# LoRaMicroClimate.net
KiCad netlist of a schematic drawn in Altium Designer
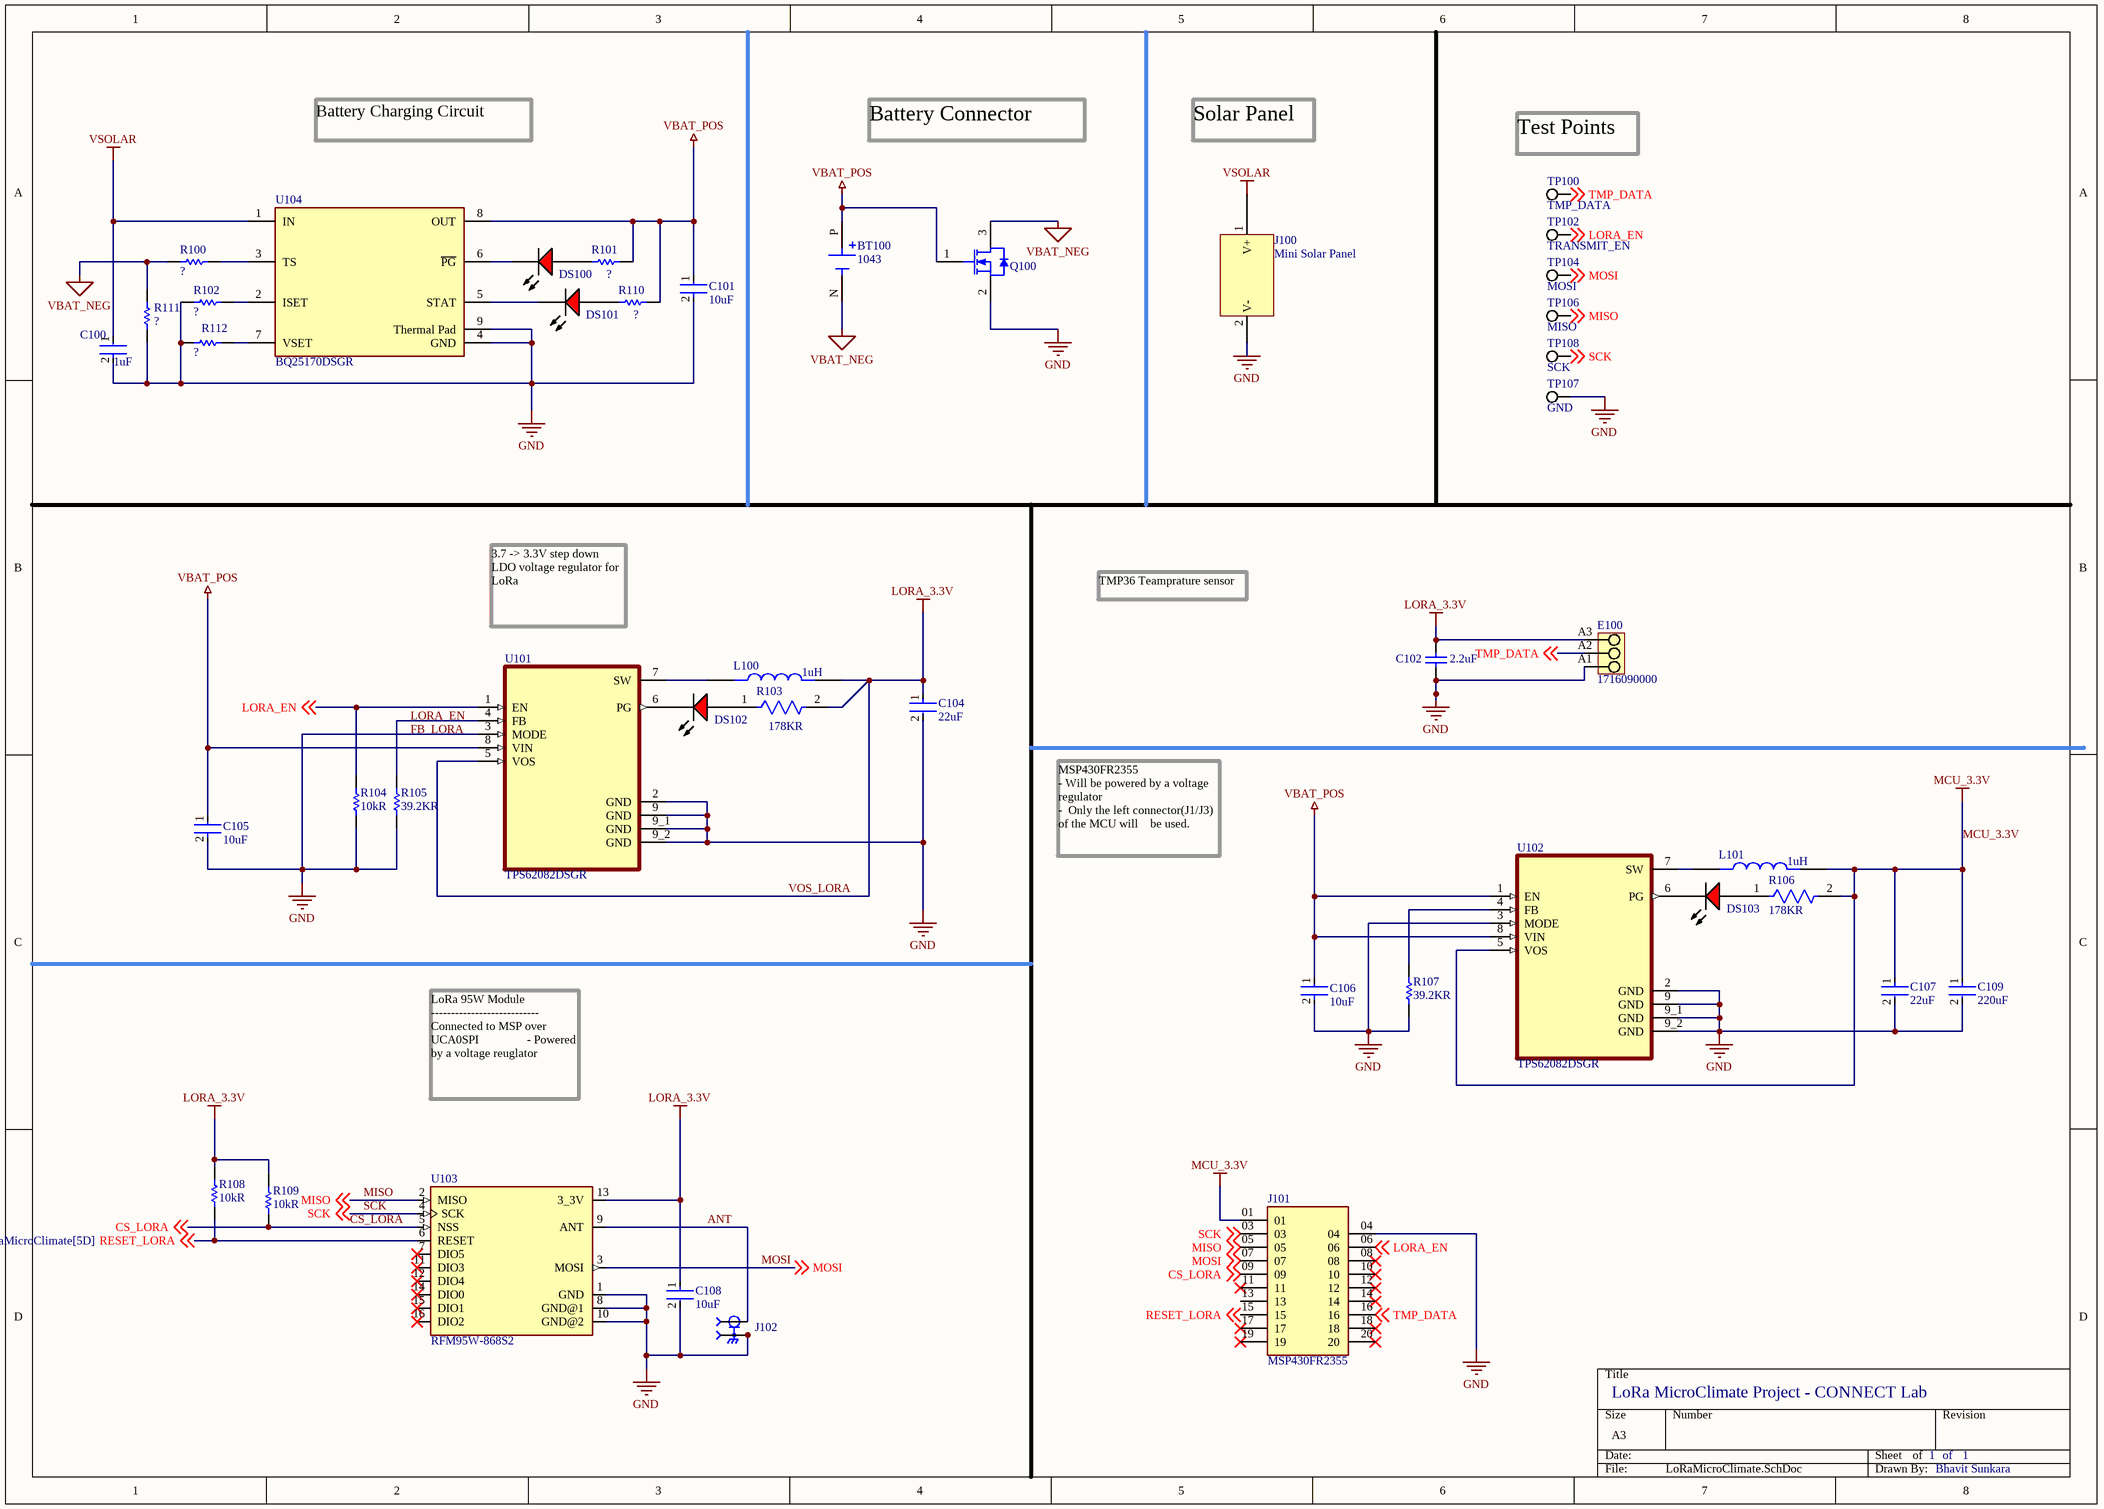
[diagram p0: LoRaMicroClimate.SchDoc]

(export (version "E")
  (design (tool "Eeschema 10.0.6"))
  (components
    (comp (ref "BT100")
      (value "1043")
      (footprint "BAT_1043")
      (description "Battery Holder (Open) 18650 1 Cell PC Pin")
      (libsource (lib "1043") (part "1043"))
    )
    (comp (ref "C100")
      (value "1uF")
      (footprint "FP-C1608-080-0_1-MFG")
      (description "Multilayer Ceramic Capacitors 10μF ±10% 10V X5R SMD 0603")
      (fields (field (name "VOLTAGE") "10V") (field (name "TOLERANCE") "10%"))
      (libsource (lib "Altium Content Vault") (part "236180d848d6139a670b325ea6854c9"))
    )
    (comp (ref "C101")
      (value "10uF")
      (footprint "FP-C1608-080-0_1-MFG")
      (description "Multilayer Ceramic Capacitors 10μF ±10% 10V X5R SMD 0603")
      (fields (field (name "VOLTAGE") "10V") (field (name "TOLERANCE") "10%"))
      (libsource (lib "Altium Content Vault") (part "236180d848d6139a670b325ea6854c9"))
    )
    (comp (ref "C102")
      (value "2.2uF")
      (footprint "CAPC2113X120X50ML20T30")
      (fields
        (field (name "PART NUMBER") "TAJR225M010RNJ")
        (field (name "MANUFACTURER") "AVX Interconnect / Elco")
      )
      (libsource (lib "Altium Content Vault") (part "CAP"))
    )
    (comp (ref "C104")
      (value "22uF")
      (footprint "FP-GRM21B-0_15-MFG")
      (description "Chip Multilayer Ceramic Capacitors for General Purpose, 0805, 22uF, X5R, 15%, 20%, 6.3V")
      (fields (field (name "VOLTAGE") "6.3V") (field (name "TOLERANCE") "20%"))
      (libsource (lib "Altium Content Vault") (part "b4654b650e69147ec39a6b967a45e02"))
    )
    (comp (ref "C105")
      (value "10uF")
      (footprint "FP-C1608-080-0_1-MFG")
      (description "Multilayer Ceramic Capacitors 10μF ±10% 10V X5R SMD 0603")
      (fields (field (name "VOLTAGE") "10V") (field (name "TOLERANCE") "10%"))
      (libsource (lib "Altium Content Vault") (part "236180d848d6139a670b325ea6854c9"))
    )
    (comp (ref "C106")
      (value "10uF")
      (footprint "FP-C1608-080-0_1-MFG")
      (description "Multilayer Ceramic Capacitors 10μF ±10% 10V X5R SMD 0603")
      (fields (field (name "VOLTAGE") "10V") (field (name "TOLERANCE") "10%"))
      (libsource (lib "Altium Content Vault") (part "236180d848d6139a670b325ea6854c9"))
    )
    (comp (ref "C107")
      (value "22uF")
      (footprint "FP-GRM21B-0_15-MFG")
      (description "Chip Multilayer Ceramic Capacitors for General Purpose, 0805, 22uF, X5R, 15%, 20%, 6.3V")
      (fields (field (name "VOLTAGE") "6.3V") (field (name "TOLERANCE") "20%"))
      (libsource (lib "Altium Content Vault") (part "b4654b650e69147ec39a6b967a45e02"))
    )
    (comp (ref "C108")
      (value "10uF")
      (footprint "FP-CL05A106MP5NUNC-MFG")
      (description "CAP CER 10UF 10V X5R 0402")
      (fields
        (field (name "OCTOPART") "https://octopart.com/cl05a106mp5nunc-samsung-22457395")
        (field (name "TOLERANCE") "20%")
      )
      (libsource (lib "Altium Content Vault") (part "b4654b650e69147ec39a6b967a45e02"))
    )
    (comp (ref "C109")
      (value "220uF")
      (footprint "FP-GRM21B-0_15-MFG")
      (description "Chip Multilayer Ceramic Capacitors for General Purpose, 0805, 22uF, X5R, 15%, 20%, 6.3V")
      (fields (field (name "VOLTAGE") "6.3V") (field (name "TOLERANCE") "20%"))
      (libsource (lib "Altium Content Vault") (part "b4654b650e69147ec39a6b967a45e02"))
    )
    (comp (ref "DS100")
      (value "HSMS-C190")
      (footprint "AVAG-HSMX-C190_V")
      (description "LED Uni-Color Red, 52 mW, 20 mA, -40 to 85 degC, 2-Pin SMD, RoHS, Tape and Reel")
      (fields (field (name "MANUFACTURER") "Avago"))
      (libsource (lib "Altium Content Vault") (part "LED-RED-AK-2"))
    )
    (comp (ref "DS101")
      (value "HSMS-C190")
      (footprint "AVAG-HSMX-C190_V")
      (description "LED Uni-Color Red, 52 mW, 20 mA, -40 to 85 degC, 2-Pin SMD, RoHS, Tape and Reel")
      (fields (field (name "MANUFACTURER") "Avago"))
      (libsource (lib "Altium Content Vault") (part "LED-RED-AK-2"))
    )
    (comp (ref "DS102")
      (value "HSMS-C190")
      (footprint "AVAG-HSMX-C190_V")
      (description "LED Uni-Color Red, 52 mW, 20 mA, -40 to 85 degC, 2-Pin SMD, RoHS, Tape and Reel")
      (fields (field (name "MANUFACTURER") "Avago"))
      (libsource (lib "Altium Content Vault") (part "LED-RED-AK-2"))
    )
    (comp (ref "DS103")
      (value "HSMS-C190")
      (footprint "AVAG-HSMX-C190_V")
      (description "LED Uni-Color Red, 52 mW, 20 mA, -40 to 85 degC, 2-Pin SMD, RoHS, Tape and Reel")
      (fields (field (name "MANUFACTURER") "Avago"))
      (libsource (lib "Altium Content Vault") (part "LED-RED-AK-2"))
    )
    (comp (ref "E100")
      (value "1716090000")
      (footprint "LM_5_08_90_03")
      (description "OMNIMATE Signal - series LM")
      (fields (field (name "MANUFACTURER") "Weidmueller"))
      (libsource (lib "Altium Content Vault") (part "Terminal_03_1x03"))
    )
    (comp (ref "J100")
      (value "Mini Solar Panel")
      (footprint "P122")
      (libsource (lib "WirelessMicroClimate") (part "P122"))
    )
    (comp (ref "J101")
      (value "MSP430FR2355")
      (footprint "SAMTEC_TSW-110-07-G-D-002")
      (fields (field (name "MP") "TSW-110-07-G-D-002"))
      (libsource (lib "TSW-110-07-G-D-002") (part "TSW-110-07-G-D-002"))
    )
    (comp (ref "J102")
      (value "SMA-J-P-X-ST-TH1")
      (footprint "SAMTEC_SMA-J-P-X-ST-TH1")
      (description "SMA STRAIGHT, THROUGH HOLE JACK- 50 OHM")
      (libsource (lib "SMA-J-P-X-ST-TH1") (part "SMA-J-P-X-ST-TH1"))
    )
    (comp (ref "L100")
      (value "1uH")
      (footprint "IND_ASPI-3012S-1R0M-T")
      (description "Inductor Power Shielded Wirewound 1uH 20% 100KHz 2.2A 0.04Ohm DCR 1212 T/R")
      (fields (field (name "MF") "Abracon Corporation") (field (name "MP") "ASPI-3012S-1R0M-T"))
      (libsource (lib "ASPI-3012S-1R0M-T") (part "ASPI-3012S-1R0M-T"))
    )
    (comp (ref "L101")
      (value "1uH")
      (footprint "IND_ASPI-3012S-1R0M-T")
      (description "Inductor Power Shielded Wirewound 1uH 20% 100KHz 2.2A 0.04Ohm DCR 1212 T/R")
      (fields (field (name "MF") "Abracon Corporation") (field (name "MP") "ASPI-3012S-1R0M-T"))
      (libsource (lib "ASPI-3012S-1R0M-T") (part "ASPI-3012S-1R0M-T"))
    )
    (comp (ref "Q100")
      (value "2N7002-T1-E3")
      (footprint "VISH-TO-236-3_A_L")
      (description "N-Channel MOSFET, 115 mA, 60 V, -55 to 150 degC, 3-Pin SOT23, RoHS, Tape and Reel")
      (fields (field (name "MANUFACTURER") "Vishay"))
      (libsource (lib "Altium Content Vault") (part "NEMOS-GSD-3"))
    )
    (comp (ref "R100")
      (value "?")
      (footprint "RESC1005X40X25LL05T10")
      (fields (field (name "PART NUMBER") "RC0402FR-0710KL") (field (name "MANUFACTURER") "Yageo / Phycomp"))
      (libsource (lib "Altium Content Vault") (part "RES"))
    )
    (comp (ref "R101")
      (value "?")
      (footprint "RESC1005X40X25LL05T10")
      (fields (field (name "PART NUMBER") "RC0402FR-0710KL") (field (name "MANUFACTURER") "Yageo / Phycomp"))
      (libsource (lib "Altium Content Vault") (part "RES"))
    )
    (comp (ref "R102")
      (value "?")
      (footprint "RESC1005X40X25LL05T10")
      (fields (field (name "PART NUMBER") "RC0402FR-0710KL") (field (name "MANUFACTURER") "Yageo / Phycomp"))
      (libsource (lib "Altium Content Vault") (part "RES"))
    )
    (comp (ref "R103")
      (value "178KR")
      (footprint "FP-CRCW0603-e3-IPC_A")
      (description "RES Thick Film, 178kΩ, 1%, 0.1W, 100ppm/°C, 0603")
      (fields (field (name "TOLERANCE") "1%"))
      (libsource (lib "Altium Content Vault") (part "1029c3af85768c4190bb7ad29bc67b5"))
    )
    (comp (ref "R104")
      (value "10kR")
      (footprint "RESC1005X40X25LL05T10")
      (fields (field (name "PART NUMBER") "RC0402FR-0710KL") (field (name "MANUFACTURER") "Yageo / Phycomp"))
      (libsource (lib "Altium Content Vault") (part "RES"))
    )
    (comp (ref "R105")
      (value "39.2KR")
      (footprint "RESC1609X50X30LL10T20")
      (fields (field (name "MANUFACTURER") "Vishay Dale") (field (name "PART NUMBER") "CRCW060339K2FKEA"))
      (libsource (lib "Altium Content Vault") (part "RES"))
    )
    (comp (ref "R106")
      (value "178KR")
      (footprint "FP-CRCW0603-e3-IPC_A")
      (description "RES Thick Film, 178kΩ, 1%, 0.1W, 100ppm/°C, 0603")
      (fields (field (name "TOLERANCE") "1%"))
      (libsource (lib "Altium Content Vault") (part "1029c3af85768c4190bb7ad29bc67b5"))
    )
    (comp (ref "R107")
      (value "39.2KR")
      (footprint "RESC1609X50X30LL10T20")
      (fields (field (name "MANUFACTURER") "Vishay Dale") (field (name "PART NUMBER") "CRCW060339K2FKEA"))
      (libsource (lib "Altium Content Vault") (part "RES"))
    )
    (comp (ref "R108")
      (value "10kR")
      (footprint "RESC1005X40X25LL05T10")
      (fields (field (name "PART NUMBER") "RC0402FR-0710KL") (field (name "MANUFACTURER") "Yageo / Phycomp"))
      (libsource (lib "Altium Content Vault") (part "RES"))
    )
    (comp (ref "R109")
      (value "10kR")
      (footprint "RESC1005X40X25LL05T10")
      (fields (field (name "PART NUMBER") "RC0402FR-0710KL") (field (name "MANUFACTURER") "Yageo / Phycomp"))
      (libsource (lib "Altium Content Vault") (part "RES"))
    )
    (comp (ref "R110")
      (value "?")
      (footprint "RESC1005X40X25LL05T10")
      (fields (field (name "PART NUMBER") "RC0402FR-0710KL") (field (name "MANUFACTURER") "Yageo / Phycomp"))
      (libsource (lib "Altium Content Vault") (part "RES"))
    )
    (comp (ref "R111")
      (value "?")
      (footprint "RESC1005X40X25LL05T10")
      (fields (field (name "PART NUMBER") "RC0402FR-0710KL") (field (name "MANUFACTURER") "Yageo / Phycomp"))
      (libsource (lib "Altium Content Vault") (part "RES"))
    )
    (comp (ref "R112")
      (value "?")
      (footprint "RESC1005X40X25LL05T10")
      (fields (field (name "PART NUMBER") "RC0402FR-0710KL") (field (name "MANUFACTURER") "Yageo / Phycomp"))
      (libsource (lib "Altium Content Vault") (part "RES"))
    )
    (comp (ref "TP100")
      (value "TMP_DATA")
      (footprint "KSTN-5019_V")
      (description "Test Point, 1 Position SMD, RoHS, Tape and Reel")
      (libsource (lib "Altium Content Vault") (part "TESTPOINT_WHITE"))
    )
    (comp (ref "TP102")
      (value "TRANSMIT_EN")
      (footprint "KSTN-5019_V")
      (description "Test Point, 1 Position SMD, RoHS, Tape and Reel")
      (libsource (lib "Altium Content Vault") (part "TESTPOINT_WHITE"))
    )
    (comp (ref "TP104")
      (value "MOSI")
      (footprint "KSTN-5019_V")
      (description "Test Point, 1 Position SMD, RoHS, Tape and Reel")
      (libsource (lib "Altium Content Vault") (part "TESTPOINT_WHITE"))
    )
    (comp (ref "TP106")
      (value "MISO")
      (footprint "KSTN-5019_V")
      (description "Test Point, 1 Position SMD, RoHS, Tape and Reel")
      (libsource (lib "Altium Content Vault") (part "TESTPOINT_WHITE"))
    )
    (comp (ref "TP107")
      (value "GND")
      (footprint "KSTN-5019_V")
      (description "Test Point, 1 Position SMD, RoHS, Tape and Reel")
      (libsource (lib "Altium Content Vault") (part "TESTPOINT_WHITE"))
    )
    (comp (ref "TP108")
      (value "SCK")
      (footprint "KSTN-5019_V")
      (description "Test Point, 1 Position SMD, RoHS, Tape and Reel")
      (libsource (lib "Altium Content Vault") (part "TESTPOINT_WHITE"))
    )
    (comp (ref "U101")
      (value "TPS62082DSGR")
      (footprint "SON50P200X200X80-9N")
      (description "1.2A High Efficient Step Down Converter in 2x2mm SON Package. 3.3 Vout (Min) 8-WSON -40 to 125")
      (fields (field (name "MF") "Texas Instruments") (field (name "DIGI-KEY_PART_NUMBER") "296-49331-1-ND"))
      (libsource (lib "TPS62082DSGR") (part "TPS62082DSGR"))
    )
    (comp (ref "U102")
      (value "TPS62082DSGR")
      (footprint "SON50P200X200X80-9N")
      (description "1.2A High Efficient Step Down Converter in 2x2mm SON Package. 3.3 Vout (Min) 8-WSON -40 to 125")
      (fields (field (name "MF") "Texas Instruments") (field (name "DIGI-KEY_PART_NUMBER") "296-49331-1-ND"))
      (libsource (lib "TPS62082DSGR") (part "TPS62082DSGR"))
    )
    (comp (ref "U103")
      (value "RFM95W-868S2")
      (footprint "XCVR_RFM95W-868S2")
      (description "Mod Txrx Lora +20dbm 868mhz Smd")
      (libsource (lib "RFM95W-868S2") (part "RFM95W-868S2"))
    )
    (comp (ref "U104")
      (value "BQ25170DSGR")
      (footprint "FP-DSG0008A-IPC_A")
      (description "800-MA LINEAR BATTERY CHARGER FO")
      (libsource (lib "Altium Content Vault") (part "8a2467e5c458e831b7d8dd803ec95f1"))
    )
  )
  (nets
    (net (code "1") (name "/ANT") (class "Default")
      (node (ref "J102") (pin "1") (pinfunction "1_1") (pintype "passive"))
      (node (ref "U103") (pin "9") (pinfunction "ANT_9") (pintype "passive"))
    )
    (net (code "2") (name "/FB_LORA") (class "Default")
      (node (ref "R105") (pin "1") (pinfunction "1_1") (pintype "passive"))
      (node (ref "U101") (pin "4") (pinfunction "FB_4") (pintype "input"))
    )
    (net (code "3") (name "CS_LORA") (class "Default")
      (node (ref "J101") (pin "09") (pinfunction "09_09") (pintype "passive"))
      (node (ref "R109") (pin "1") (pinfunction "1_1") (pintype "passive"))
      (node (ref "U103") (pin "5") (pinfunction "NSS_5") (pintype "input"))
    )
    (net (code "4") (name "GND") (class "Default")
      (node (ref "C100") (pin "2") (pinfunction "2_2") (pintype "passive"))
      (node (ref "C101") (pin "2") (pinfunction "2_2") (pintype "passive"))
      (node (ref "C102") (pin "1") (pinfunction "1_1") (pintype "passive"))
      (node (ref "C104") (pin "2") (pinfunction "2_2") (pintype "passive"))
      (node (ref "C105") (pin "2") (pinfunction "2_2") (pintype "passive"))
      (node (ref "C106") (pin "2") (pinfunction "2_2") (pintype "passive"))
      (node (ref "C107") (pin "2") (pinfunction "2_2") (pintype "passive"))
      (node (ref "C108") (pin "2") (pinfunction "2_2") (pintype "passive"))
      (node (ref "C109") (pin "2") (pinfunction "2_2") (pintype "passive"))
      (node (ref "E100") (pin "A1") (pinfunction "A1_A1") (pintype "passive"))
      (node (ref "J100") (pin "2") (pinfunction "V-_2") (pintype "passive"))
      (node (ref "J101") (pin "04") (pinfunction "04_04") (pintype "passive"))
      (node (ref "J102") (pin "2") (pinfunction "2_2") (pintype "passive"))
      (node (ref "J102") (pin "3") (pinfunction "2_3") (pintype "passive"))
      (node (ref "J102") (pin "4") (pinfunction "2_4") (pintype "passive"))
      (node (ref "J102") (pin "5") (pinfunction "2_5") (pintype "passive"))
      (node (ref "Q100") (pin "2") (pinfunction "S_2") (pintype "passive"))
      (node (ref "R102") (pin "1") (pinfunction "1_1") (pintype "passive"))
      (node (ref "R104") (pin "2") (pinfunction "2_2") (pintype "passive"))
      (node (ref "R105") (pin "2") (pinfunction "2_2") (pintype "passive"))
      (node (ref "R107") (pin "2") (pinfunction "2_2") (pintype "passive"))
      (node (ref "R111") (pin "1") (pinfunction "1_1") (pintype "passive"))
      (node (ref "R112") (pin "1") (pinfunction "1_1") (pintype "passive"))
      (node (ref "TP107") (pin "1") (pinfunction "1_1") (pintype "passive"))
      (node (ref "U101") (pin "2") (pinfunction "GND_2") (pintype "power_in"))
      (node (ref "U101") (pin "3") (pinfunction "MODE_3") (pintype "input"))
      (node (ref "U101") (pin "9") (pinfunction "GND_9") (pintype "power_in"))
      (node (ref "U101") (pin "9_1") (pinfunction "GND_9_1") (pintype "power_in"))
      (node (ref "U101") (pin "9_2") (pinfunction "GND_9_2") (pintype "power_in"))
      (node (ref "U102") (pin "2") (pinfunction "GND_2") (pintype "power_in"))
      (node (ref "U102") (pin "3") (pinfunction "MODE_3") (pintype "input"))
      (node (ref "U102") (pin "9") (pinfunction "GND_9") (pintype "power_in"))
      (node (ref "U102") (pin "9_1") (pinfunction "GND_9_1") (pintype "power_in"))
      (node (ref "U102") (pin "9_2") (pinfunction "GND_9_2") (pintype "power_in"))
      (node (ref "U103") (pin "1") (pinfunction "GND_1") (pintype "power_in"))
      (node (ref "U103") (pin "10") (pinfunction "GND@2_10") (pintype "power_in"))
      (node (ref "U103") (pin "8") (pinfunction "GND@1_8") (pintype "power_in"))
      (node (ref "U104") (pin "4") (pinfunction "GND_4") (pintype "power_in"))
      (node (ref "U104") (pin "9") (pinfunction "Thermal_Pad_9") (pintype "power_in"))
    )
    (net (code "5") (name "LORA_3.3V") (class "Default")
      (node (ref "C102") (pin "2") (pinfunction "2_2") (pintype "passive"))
      (node (ref "C104") (pin "1") (pinfunction "1_1") (pintype "passive"))
      (node (ref "C108") (pin "1") (pinfunction "1_1") (pintype "passive"))
      (node (ref "E100") (pin "A3") (pinfunction "A3_A3") (pintype "passive"))
      (node (ref "L100") (pin "2") (pinfunction "2_2") (pintype "passive"))
      (node (ref "R103") (pin "2") (pinfunction "2_2") (pintype "passive"))
      (node (ref "R108") (pin "2") (pinfunction "2_2") (pintype "passive"))
      (node (ref "R109") (pin "2") (pinfunction "2_2") (pintype "passive"))
      (node (ref "U101") (pin "5") (pinfunction "VOS_5") (pintype "input"))
      (node (ref "U103") (pin "13") (pinfunction "3_3V_13") (pintype "power_in"))
    )
    (net (code "6") (name "LORA_EN") (class "Default")
      (node (ref "J101") (pin "06") (pinfunction "06_06") (pintype "passive"))
      (node (ref "R104") (pin "1") (pinfunction "1_1") (pintype "passive"))
      (node (ref "TP102") (pin "1") (pinfunction "1_1") (pintype "passive"))
      (node (ref "U101") (pin "1") (pinfunction "EN_1") (pintype "input"))
    )
    (net (code "7") (name "MCU_3.3V") (class "Default")
      (node (ref "C107") (pin "1") (pinfunction "1_1") (pintype "passive"))
      (node (ref "C109") (pin "1") (pinfunction "1_1") (pintype "passive"))
      (node (ref "J101") (pin "01") (pinfunction "01_01") (pintype "passive"))
      (node (ref "L101") (pin "2") (pinfunction "2_2") (pintype "passive"))
      (node (ref "R106") (pin "2") (pinfunction "2_2") (pintype "passive"))
      (node (ref "U102") (pin "5") (pinfunction "VOS_5") (pintype "input"))
    )
    (net (code "8") (name "MISO") (class "Default")
      (node (ref "J101") (pin "05") (pinfunction "05_05") (pintype "passive"))
      (node (ref "TP106") (pin "1") (pinfunction "1_1") (pintype "passive"))
      (node (ref "U103") (pin "2") (pinfunction "MISO_2") (pintype "input"))
    )
    (net (code "9") (name "MOSI") (class "Default")
      (node (ref "J101") (pin "07") (pinfunction "07_07") (pintype "passive"))
      (node (ref "TP104") (pin "1") (pinfunction "1_1") (pintype "passive"))
      (node (ref "U103") (pin "3") (pinfunction "MOSI_3") (pintype "output"))
    )
    (net (code "10") (name "Net-(DS100-A)") (class "Default")
      (node (ref "DS100") (pin "1") (pinfunction "A_1") (pintype "passive"))
      (node (ref "R101") (pin "1") (pinfunction "1_1") (pintype "passive"))
    )
    (net (code "11") (name "Net-(DS100-K)") (class "Default")
      (node (ref "DS100") (pin "2") (pinfunction "K_2") (pintype "passive"))
      (node (ref "U104") (pin "6") (pinfunction "~{PG}_6") (pintype "open_collector"))
    )
    (net (code "12") (name "Net-(DS101-A)") (class "Default")
      (node (ref "DS101") (pin "1") (pinfunction "A_1") (pintype "passive"))
      (node (ref "R110") (pin "1") (pinfunction "1_1") (pintype "passive"))
    )
    (net (code "13") (name "Net-(DS101-K)") (class "Default")
      (node (ref "DS101") (pin "2") (pinfunction "K_2") (pintype "passive"))
      (node (ref "U104") (pin "5") (pinfunction "STAT_5") (pintype "open_collector"))
    )
    (net (code "14") (name "Net-(DS102-A)") (class "Default")
      (node (ref "DS102") (pin "1") (pinfunction "A_1") (pintype "passive"))
      (node (ref "R103") (pin "1") (pinfunction "1_1") (pintype "passive"))
    )
    (net (code "15") (name "Net-(DS102-K)") (class "Default")
      (node (ref "DS102") (pin "2") (pinfunction "K_2") (pintype "passive"))
      (node (ref "U101") (pin "6") (pinfunction "PG_6") (pintype "output"))
    )
    (net (code "16") (name "Net-(DS103-A)") (class "Default")
      (node (ref "DS103") (pin "1") (pinfunction "A_1") (pintype "passive"))
      (node (ref "R106") (pin "1") (pinfunction "1_1") (pintype "passive"))
    )
    (net (code "17") (name "Net-(DS103-K)") (class "Default")
      (node (ref "DS103") (pin "2") (pinfunction "K_2") (pintype "passive"))
      (node (ref "U102") (pin "6") (pinfunction "PG_6") (pintype "output"))
    )
    (net (code "18") (name "Net-(U101-SW)") (class "Default")
      (node (ref "L100") (pin "1") (pinfunction "1_1") (pintype "passive"))
      (node (ref "U101") (pin "7") (pinfunction "SW_7") (pintype "power_in"))
    )
    (net (code "19") (name "Net-(U102-FB)") (class "Default")
      (node (ref "R107") (pin "1") (pinfunction "1_1") (pintype "passive"))
      (node (ref "U102") (pin "4") (pinfunction "FB_4") (pintype "input"))
    )
    (net (code "20") (name "Net-(U102-SW)") (class "Default")
      (node (ref "L101") (pin "1") (pinfunction "1_1") (pintype "passive"))
      (node (ref "U102") (pin "7") (pinfunction "SW_7") (pintype "power_in"))
    )
    (net (code "21") (name "Net-(U104-ISET)") (class "Default")
      (node (ref "R102") (pin "2") (pinfunction "2_2") (pintype "passive"))
      (node (ref "U104") (pin "2") (pinfunction "ISET_2") (pintype "passive"))
    )
    (net (code "22") (name "Net-(U104-TS)") (class "Default")
      (node (ref "R100") (pin "1") (pinfunction "1_1") (pintype "passive"))
      (node (ref "U104") (pin "3") (pinfunction "TS_3") (pintype "passive"))
    )
    (net (code "23") (name "Net-(U104-VSET)") (class "Default")
      (node (ref "R112") (pin "2") (pinfunction "2_2") (pintype "passive"))
      (node (ref "U104") (pin "7") (pinfunction "VSET_7") (pintype "passive"))
    )
    (net (code "24") (name "RESET_LORA") (class "Default")
      (node (ref "J101") (pin "15") (pinfunction "15_15") (pintype "passive"))
      (node (ref "R108") (pin "1") (pinfunction "1_1") (pintype "passive"))
      (node (ref "U103") (pin "6") (pinfunction "RESET_6") (pintype "bidirectional"))
    )
    (net (code "25") (name "SCK") (class "Default")
      (node (ref "J101") (pin "03") (pinfunction "03_03") (pintype "passive"))
      (node (ref "TP108") (pin "1") (pinfunction "1_1") (pintype "passive"))
      (node (ref "U103") (pin "4") (pinfunction "SCK_4") (pintype "input"))
    )
    (net (code "26") (name "TMP_DATA") (class "Default")
      (node (ref "E100") (pin "A2") (pinfunction "A2_A2") (pintype "passive"))
      (node (ref "J101") (pin "16") (pinfunction "16_16") (pintype "passive"))
      (node (ref "TP100") (pin "1") (pinfunction "1_1") (pintype "passive"))
    )
    (net (code "27") (name "VBAT_NEG") (class "Default")
      (node (ref "BT100") (pin "N") (pinfunction "N_N") (pintype "passive"))
      (node (ref "Q100") (pin "3") (pinfunction "D_3") (pintype "passive"))
      (node (ref "R100") (pin "2") (pinfunction "2_2") (pintype "passive"))
      (node (ref "R111") (pin "2") (pinfunction "2_2") (pintype "passive"))
    )
    (net (code "28") (name "VBAT_POS") (class "Default")
      (node (ref "BT100") (pin "P") (pinfunction "P_P") (pintype "passive"))
      (node (ref "C101") (pin "1") (pinfunction "1_1") (pintype "passive"))
      (node (ref "C105") (pin "1") (pinfunction "1_1") (pintype "passive"))
      (node (ref "C106") (pin "1") (pinfunction "1_1") (pintype "passive"))
      (node (ref "Q100") (pin "1") (pinfunction "G_1") (pintype "passive"))
      (node (ref "R101") (pin "2") (pinfunction "2_2") (pintype "passive"))
      (node (ref "R110") (pin "2") (pinfunction "2_2") (pintype "passive"))
      (node (ref "U101") (pin "8") (pinfunction "VIN_8") (pintype "input"))
      (node (ref "U102") (pin "1") (pinfunction "EN_1") (pintype "input"))
      (node (ref "U102") (pin "8") (pinfunction "VIN_8") (pintype "input"))
      (node (ref "U104") (pin "8") (pinfunction "OUT_8") (pintype "passive"))
    )
    (net (code "29") (name "VSOLAR") (class "Default")
      (node (ref "C100") (pin "1") (pinfunction "1_1") (pintype "passive"))
      (node (ref "J100") (pin "1") (pinfunction "V+_1") (pintype "passive"))
      (node (ref "U104") (pin "1") (pinfunction "IN_1") (pintype "power_in"))
    )
    (net (code "30") (name "unconnected-(J101-Pad08)") (class "Default")
      (node (ref "J101") (pin "08") (pinfunction "08_08") (pintype "passive+no_connect"))
    )
    (net (code "31") (name "unconnected-(J101-Pad10)") (class "Default")
      (node (ref "J101") (pin "10") (pinfunction "10_10") (pintype "passive+no_connect"))
    )
    (net (code "32") (name "unconnected-(J101-Pad11)") (class "Default")
      (node (ref "J101") (pin "11") (pinfunction "11_11") (pintype "passive+no_connect"))
    )
    (net (code "33") (name "unconnected-(J101-Pad12)") (class "Default")
      (node (ref "J101") (pin "12") (pinfunction "12_12") (pintype "passive+no_connect"))
    )
    (net (code "34") (name "unconnected-(J101-Pad13)") (class "Default")
      (node (ref "J101") (pin "13") (pinfunction "13_13") (pintype "passive"))
    )
    (net (code "35") (name "unconnected-(J101-Pad14)") (class "Default")
      (node (ref "J101") (pin "14") (pinfunction "14_14") (pintype "passive+no_connect"))
    )
    (net (code "36") (name "unconnected-(J101-Pad17)") (class "Default")
      (node (ref "J101") (pin "17") (pinfunction "17_17") (pintype "passive+no_connect"))
    )
    (net (code "37") (name "unconnected-(J101-Pad18)") (class "Default")
      (node (ref "J101") (pin "18") (pinfunction "18_18") (pintype "passive+no_connect"))
    )
    (net (code "38") (name "unconnected-(J101-Pad19)") (class "Default")
      (node (ref "J101") (pin "19") (pinfunction "19_19") (pintype "passive+no_connect"))
    )
    (net (code "39") (name "unconnected-(J101-Pad20)") (class "Default")
      (node (ref "J101") (pin "20") (pinfunction "20_20") (pintype "passive+no_connect"))
    )
    (net (code "40") (name "unconnected-(U103-DIO0-Pad14)") (class "Default")
      (node (ref "U103") (pin "14") (pinfunction "DIO0_14") (pintype "bidirectional+no_connect"))
    )
    (net (code "41") (name "unconnected-(U103-DIO1-Pad15)") (class "Default")
      (node (ref "U103") (pin "15") (pinfunction "DIO1_15") (pintype "bidirectional+no_connect"))
    )
    (net (code "42") (name "unconnected-(U103-DIO2-Pad16)") (class "Default")
      (node (ref "U103") (pin "16") (pinfunction "DIO2_16") (pintype "bidirectional+no_connect"))
    )
    (net (code "43") (name "unconnected-(U103-DIO3-Pad11)") (class "Default")
      (node (ref "U103") (pin "11") (pinfunction "DIO3_11") (pintype "bidirectional+no_connect"))
    )
    (net (code "44") (name "unconnected-(U103-DIO4-Pad12)") (class "Default")
      (node (ref "U103") (pin "12") (pinfunction "DIO4_12") (pintype "bidirectional+no_connect"))
    )
    (net (code "45") (name "unconnected-(U103-DIO5-Pad7)") (class "Default")
      (node (ref "U103") (pin "7") (pinfunction "DIO5_7") (pintype "bidirectional+no_connect"))
    )
  )
)
